# sd2snes_revH.net
KiCad netlist of a schematic drawn in EAGLE
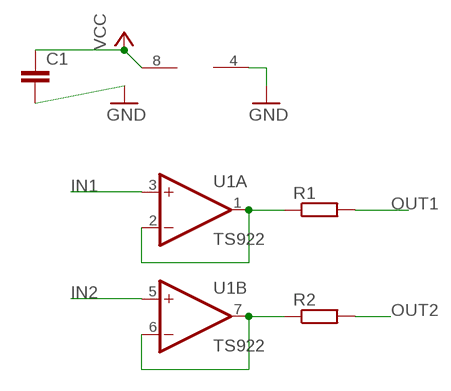
[diagram p0: schematic, sheet 1]

(export (version "E")
  (design (tool "Eeschema 10.0.6"))
  (components
    (comp (ref "C1")
      (value "C-EUC0603")
      (footprint "eagle-import:C0603")
      (libsource (lib "eagle-import") (part "C-EUC0603"))
    )
    (comp (ref "R1")
      (value "R-EU_R0603")
      (footprint "eagle-import:R0603")
      (libsource (lib "eagle-import") (part "R-EU_R0603"))
    )
    (comp (ref "R2")
      (value "R-EU_R0603")
      (footprint "eagle-import:R0603")
      (libsource (lib "eagle-import") (part "R-EU_R0603"))
    )
    (comp (ref "U1")
      (value "TS922")
      (footprint "eagle-import:SO08")
      (libsource (lib "eagle-import") (part "TL072D"))
    )
  )
  (nets
    (net (code "1") (name "/IN1") (class "Default")
      (node (ref "U1") (pin "3") (pinfunction "+IN_3") (pintype "input"))
    )
    (net (code "2") (name "/IN2") (class "Default")
      (node (ref "U1") (pin "5") (pinfunction "+IN_5") (pintype "input"))
    )
    (net (code "3") (name "/OUT1") (class "Default")
      (node (ref "R1") (pin "2") (pinfunction "2_2") (pintype "passive"))
    )
    (net (code "4") (name "/OUT2") (class "Default")
      (node (ref "R2") (pin "2") (pinfunction "2_2") (pintype "passive"))
    )
    (net (code "5") (name "GND") (class "Default")
      (node (ref "C1") (pin "2") (pinfunction "2_2") (pintype "passive"))
      (node (ref "U1") (pin "4") (pinfunction "V-_4") (pintype "power_in"))
    )
    (net (code "6") (name "Net-(U1A--IN)") (class "Default")
      (node (ref "R1") (pin "1") (pinfunction "1_1") (pintype "passive"))
      (node (ref "U1") (pin "1") (pinfunction "OUT_1") (pintype "output"))
      (node (ref "U1") (pin "2") (pinfunction "-IN_2") (pintype "input"))
    )
    (net (code "7") (name "Net-(U1B--IN)") (class "Default")
      (node (ref "R2") (pin "1") (pinfunction "1_1") (pintype "passive"))
      (node (ref "U1") (pin "6") (pinfunction "-IN_6") (pintype "input"))
      (node (ref "U1") (pin "7") (pinfunction "OUT_7") (pintype "output"))
    )
    (net (code "8") (name "VCC") (class "Default")
      (node (ref "C1") (pin "1") (pinfunction "1_1") (pintype "passive"))
      (node (ref "U1") (pin "8") (pinfunction "V+_8") (pintype "power_in"))
    )
  )
)
